# Dozimetr.net
KiCad netlist of a schematic drawn in EAGLE
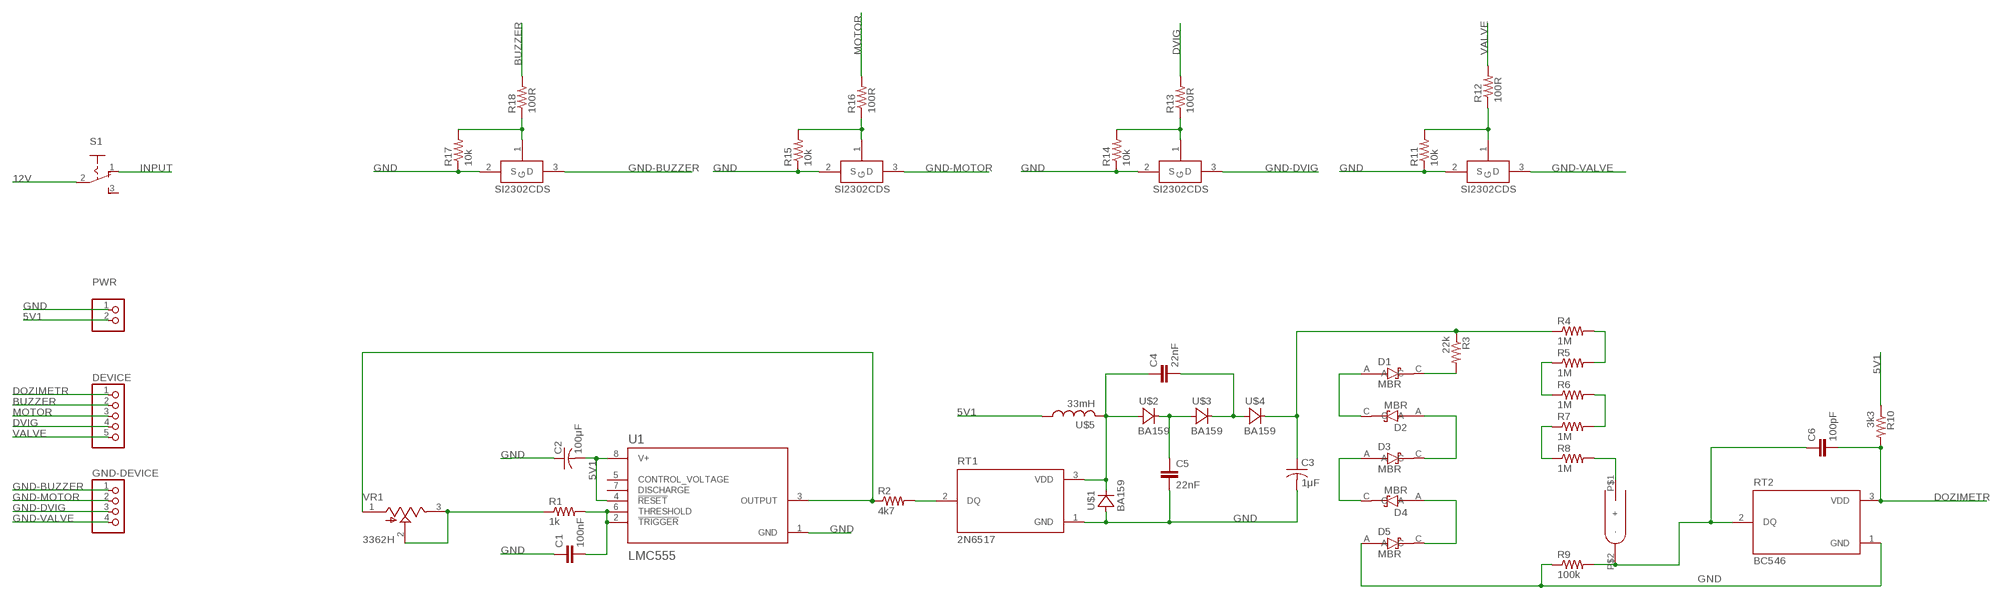
[diagram p0: schematic, sheet 1]

(export (version "E")
  (design (tool "Eeschema 10.0.6"))
  (components
    (comp (ref "C1")
      (value "100nF")
      (footprint "eagle-import:C0603")
      (libsource (lib "eagle-import") (part "C-EUC0603"))
    )
    (comp (ref "C2")
      (value "100μF")
      (footprint "eagle-import:ECAP100-CMD")
      (libsource (lib "eagle-import") (part "ECAPECAP100"))
    )
    (comp (ref "C3")
      (value "1μF")
      (footprint "eagle-import:ECAP1MK")
      (libsource (lib "eagle-import") (part "ECAP"))
    )
    (comp (ref "C4")
      (value "22nF")
      (footprint "eagle-import:C1210")
      (libsource (lib "eagle-import") (part "C-EUC1210"))
    )
    (comp (ref "C5")
      (value "22nF")
      (footprint "eagle-import:C1210")
      (libsource (lib "eagle-import") (part "C-EUC1210"))
    )
    (comp (ref "C6")
      (value "100pF")
      (footprint "eagle-import:C0603")
      (libsource (lib "eagle-import") (part "C-EUC0603"))
    )
    (comp (ref "D1")
      (value "MBR")
      (footprint "eagle-import:SOD123")
      (fields (field (name "MF") "ON Semiconductor") (field (name "MP") "MBR0520LT1G"))
      (libsource (lib "eagle-import") (part "DIODE-MBR"))
    )
    (comp (ref "D2")
      (value "MBR")
      (footprint "eagle-import:SOD123")
      (fields (field (name "MF") "ON Semiconductor") (field (name "MP") "MBR0520LT1G"))
      (libsource (lib "eagle-import") (part "DIODE-MBR"))
    )
    (comp (ref "D3")
      (value "MBR")
      (footprint "eagle-import:SOD123")
      (fields (field (name "MF") "ON Semiconductor") (field (name "MP") "MBR0520LT1G"))
      (libsource (lib "eagle-import") (part "DIODE-MBR"))
    )
    (comp (ref "D4")
      (value "MBR")
      (footprint "eagle-import:SOD123")
      (fields (field (name "MF") "ON Semiconductor") (field (name "MP") "MBR0520LT1G"))
      (libsource (lib "eagle-import") (part "DIODE-MBR"))
    )
    (comp (ref "D5")
      (value "MBR")
      (footprint "eagle-import:SOD123")
      (fields (field (name "MF") "ON Semiconductor") (field (name "MP") "MBR0520LT1G"))
      (libsource (lib "eagle-import") (part "DIODE-MBR"))
    )
    (comp (ref "DEVICE")
      (value "PINHD-1X5")
      (footprint "eagle-import:1X05")
      (libsource (lib "eagle-import") (part "PINHD-1X5"))
    )
    (comp (ref "DOSE")
      (value "DOSIM_SBM20-1")
      (footprint "eagle-import:DOSIM_SBM20-1")
      (libsource (lib "eagle-import") (part "DOSIM_SBM20-1"))
    )
    (comp (ref "GND-DEVICE")
      (value "PINHD-1X4")
      (footprint "eagle-import:1X04")
      (libsource (lib "eagle-import") (part "PINHD-1X4"))
    )
    (comp (ref "PWR")
      (value "PINHD-1X2")
      (footprint "eagle-import:1X02")
      (libsource (lib "eagle-import") (part "PINHD-1X2"))
    )
    (comp (ref "R1")
      (value "1k")
      (footprint "eagle-import:R0603")
      (libsource (lib "eagle-import") (part "R-US_R0603"))
    )
    (comp (ref "R2")
      (value "4k7")
      (footprint "eagle-import:R0603")
      (libsource (lib "eagle-import") (part "R-US_R0603"))
    )
    (comp (ref "R3")
      (value "22k")
      (footprint "eagle-import:R0603")
      (libsource (lib "eagle-import") (part "R-US_R0603"))
    )
    (comp (ref "R4")
      (value "1M")
      (footprint "eagle-import:R0603")
      (libsource (lib "eagle-import") (part "R-US_R0603"))
    )
    (comp (ref "R5")
      (value "1M")
      (footprint "eagle-import:R0603")
      (libsource (lib "eagle-import") (part "R-US_R0603"))
    )
    (comp (ref "R6")
      (value "1M")
      (footprint "eagle-import:R0603")
      (libsource (lib "eagle-import") (part "R-US_R0603"))
    )
    (comp (ref "R7")
      (value "1M")
      (footprint "eagle-import:R0603")
      (libsource (lib "eagle-import") (part "R-US_R0603"))
    )
    (comp (ref "R8")
      (value "1M")
      (footprint "eagle-import:R0603")
      (libsource (lib "eagle-import") (part "R-US_R0603"))
    )
    (comp (ref "R9")
      (value "100k")
      (footprint "eagle-import:R0603")
      (libsource (lib "eagle-import") (part "R-US_R0603"))
    )
    (comp (ref "R10")
      (value "3k3")
      (footprint "eagle-import:R0603")
      (libsource (lib "eagle-import") (part "R-US_R0603"))
    )
    (comp (ref "R11")
      (value "10k")
      (footprint "eagle-import:R0603")
      (libsource (lib "eagle-import") (part "R-US_R0603"))
    )
    (comp (ref "R12")
      (value "100R")
      (footprint "eagle-import:R0603")
      (libsource (lib "eagle-import") (part "R-US_R0603"))
    )
    (comp (ref "R13")
      (value "100R")
      (footprint "eagle-import:R0603")
      (libsource (lib "eagle-import") (part "R-US_R0603"))
    )
    (comp (ref "R14")
      (value "10k")
      (footprint "eagle-import:R0603")
      (libsource (lib "eagle-import") (part "R-US_R0603"))
    )
    (comp (ref "R15")
      (value "10k")
      (footprint "eagle-import:R0603")
      (libsource (lib "eagle-import") (part "R-US_R0603"))
    )
    (comp (ref "R16")
      (value "100R")
      (footprint "eagle-import:R0603")
      (libsource (lib "eagle-import") (part "R-US_R0603"))
    )
    (comp (ref "R17")
      (value "10k")
      (footprint "eagle-import:R0603")
      (libsource (lib "eagle-import") (part "R-US_R0603"))
    )
    (comp (ref "R18")
      (value "100R")
      (footprint "eagle-import:R0603")
      (libsource (lib "eagle-import") (part "R-US_R0603"))
    )
    (comp (ref "RT1")
      (value "2N6517")
      (footprint "eagle-import:TO92_TO226")
      (fields (field (name "MF") "Maxim Integrated") (field (name "MP") "DS1820"))
      (libsource (lib "eagle-import") (part "2N6517"))
    )
    (comp (ref "RT2")
      (value "BC546")
      (footprint "eagle-import:TO92_TO226")
      (fields (field (name "MF") "Maxim Integrated") (field (name "MP") "DS1820"))
      (libsource (lib "eagle-import") (part "BC546"))
    )
    (comp (ref "S1")
      (value "SWITCH-BIG")
      (footprint "eagle-import:SWITCH-BIG")
      (libsource (lib "eagle-import") (part "SWITCH-BIG"))
    )
    (comp (ref "SI2302-1")
      (value "SI2302CDS")
      (footprint "eagle-import:SOT23-3")
      (libsource (lib "eagle-import") (part "SI2302CDS"))
    )
    (comp (ref "SI2302-2")
      (value "SI2302CDS")
      (footprint "eagle-import:SOT23-3")
      (libsource (lib "eagle-import") (part "SI2302CDS"))
    )
    (comp (ref "SI2302-3")
      (value "SI2302CDS")
      (footprint "eagle-import:SOT23-3")
      (libsource (lib "eagle-import") (part "SI2302CDS"))
    )
    (comp (ref "SI2302-4")
      (value "SI2302CDS")
      (footprint "eagle-import:SOT23-3")
      (libsource (lib "eagle-import") (part "SI2302CDS"))
    )
    (comp (ref "U$1")
      (value "BA159")
      (footprint "eagle-import:BA159")
      (libsource (lib "eagle-import") (part "BA159"))
    )
    (comp (ref "U$2")
      (value "BA159")
      (footprint "eagle-import:BA159")
      (libsource (lib "eagle-import") (part "BA159"))
    )
    (comp (ref "U$3")
      (value "BA159")
      (footprint "eagle-import:BA159")
      (libsource (lib "eagle-import") (part "BA159"))
    )
    (comp (ref "U$4")
      (value "BA159")
      (footprint "eagle-import:BA159")
      (libsource (lib "eagle-import") (part "BA159"))
    )
    (comp (ref "U$5")
      (value "33mH")
      (footprint "eagle-import:RCH114NP_-")
      (libsource (lib "eagle-import") (part "RCH114NP"))
    )
    (comp (ref "U1")
      (value "LMC555")
      (footprint "eagle-import:SOIC127P599X175-8N")
      (fields (field (name "MF") "Texas Instruments") (field (name "MP") "LMC555CMX"))
      (libsource (lib "eagle-import") (part "LMC555CMX/NOPB"))
    )
    (comp (ref "VR1")
      (value "3362H")
      (footprint "eagle-import:TRIM_3362H-1-502LF")
      (fields (field (name "MF") "Bourns") (field (name "MP") "3362P-1-502LF"))
      (libsource (lib "eagle-import") (part "3362H-1-502LF"))
    )
  )
  (nets
    (net (code "1") (name "/5V1") (class "Default")
      (node (ref "C2") (pin "P$2") (pinfunction "2_P$2") (pintype "passive"))
      (node (ref "PWR") (pin "2") (pinfunction "2_2") (pintype "passive"))
      (node (ref "R10") (pin "1") (pinfunction "1_1") (pintype "passive"))
      (node (ref "U$5") (pin "P$1") (pinfunction "1_P$1") (pintype "passive"))
      (node (ref "U1") (pin "4") (pinfunction "~{RESET}_4") (pintype "input"))
      (node (ref "U1") (pin "8") (pinfunction "V+_8") (pintype "power_in"))
    )
    (net (code "2") (name "/12V") (class "Default")
      (node (ref "S1") (pin "2") (pinfunction "P_2") (pintype "passive"))
    )
    (net (code "3") (name "/BUZZER") (class "Default")
      (node (ref "DEVICE") (pin "2") (pinfunction "2_2") (pintype "passive"))
      (node (ref "R18") (pin "2") (pinfunction "2_2") (pintype "passive"))
    )
    (net (code "4") (name "/DOZIMETR") (class "Default")
      (node (ref "C6") (pin "2") (pinfunction "2_2") (pintype "passive"))
      (node (ref "DEVICE") (pin "1") (pinfunction "1_1") (pintype "passive"))
      (node (ref "R10") (pin "2") (pinfunction "2_2") (pintype "passive"))
      (node (ref "RT2") (pin "3") (pinfunction "VDD_3") (pintype "power_in"))
    )
    (net (code "5") (name "/DVIG") (class "Default")
      (node (ref "DEVICE") (pin "4") (pinfunction "4_4") (pintype "passive"))
      (node (ref "R13") (pin "2") (pinfunction "2_2") (pintype "passive"))
    )
    (net (code "6") (name "/GND") (class "Default")
      (node (ref "C1") (pin "1") (pinfunction "1_1") (pintype "passive"))
      (node (ref "C2") (pin "P$1") (pinfunction "1_P$1") (pintype "passive"))
      (node (ref "C3") (pin "P$2") (pinfunction "2_P$2") (pintype "passive"))
      (node (ref "C5") (pin "2") (pinfunction "2_2") (pintype "passive"))
      (node (ref "D5") (pin "A") (pinfunction "A_A") (pintype "passive"))
      (node (ref "PWR") (pin "1") (pinfunction "1_1") (pintype "passive"))
      (node (ref "R11") (pin "1") (pinfunction "1_1") (pintype "passive"))
      (node (ref "R14") (pin "1") (pinfunction "1_1") (pintype "passive"))
      (node (ref "R15") (pin "1") (pinfunction "1_1") (pintype "passive"))
      (node (ref "R17") (pin "1") (pinfunction "1_1") (pintype "passive"))
      (node (ref "R9") (pin "1") (pinfunction "1_1") (pintype "passive"))
      (node (ref "RT1") (pin "1") (pinfunction "GND_1") (pintype "power_in"))
      (node (ref "RT2") (pin "1") (pinfunction "GND_1") (pintype "power_in"))
      (node (ref "SI2302-1") (pin "2") (pinfunction "S_2") (pintype "bidirectional"))
      (node (ref "SI2302-2") (pin "2") (pinfunction "S_2") (pintype "bidirectional"))
      (node (ref "SI2302-3") (pin "2") (pinfunction "S_2") (pintype "bidirectional"))
      (node (ref "SI2302-4") (pin "2") (pinfunction "S_2") (pintype "bidirectional"))
      (node (ref "U$1") (pin "P$1") (pinfunction "A_P$1") (pintype "passive"))
      (node (ref "U1") (pin "1") (pinfunction "GND_1") (pintype "power_in"))
    )
    (net (code "7") (name "/GND-BUZZER") (class "Default")
      (node (ref "GND-DEVICE") (pin "1") (pinfunction "1_1") (pintype "passive"))
      (node (ref "SI2302-1") (pin "3") (pinfunction "D_3") (pintype "bidirectional"))
    )
    (net (code "8") (name "/GND-DVIG") (class "Default")
      (node (ref "GND-DEVICE") (pin "3") (pinfunction "3_3") (pintype "passive"))
      (node (ref "SI2302-3") (pin "3") (pinfunction "D_3") (pintype "bidirectional"))
    )
    (net (code "9") (name "/GND-MOTOR") (class "Default")
      (node (ref "GND-DEVICE") (pin "2") (pinfunction "2_2") (pintype "passive"))
      (node (ref "SI2302-2") (pin "3") (pinfunction "D_3") (pintype "bidirectional"))
    )
    (net (code "10") (name "/GND-VALVE") (class "Default")
      (node (ref "GND-DEVICE") (pin "4") (pinfunction "4_4") (pintype "passive"))
      (node (ref "SI2302-4") (pin "3") (pinfunction "D_3") (pintype "bidirectional"))
    )
    (net (code "11") (name "/INPUT") (class "Default")
      (node (ref "S1") (pin "1") (pinfunction "O_1") (pintype "passive"))
    )
    (net (code "12") (name "/MOTOR") (class "Default")
      (node (ref "DEVICE") (pin "3") (pinfunction "3_3") (pintype "passive"))
      (node (ref "R16") (pin "2") (pinfunction "2_2") (pintype "passive"))
    )
    (net (code "13") (name "/VALVE") (class "Default")
      (node (ref "DEVICE") (pin "5") (pinfunction "5_5") (pintype "passive"))
      (node (ref "R12") (pin "2") (pinfunction "2_2") (pintype "passive"))
    )
    (net (code "14") (name "Net-(C3-1)") (class "Default")
      (node (ref "C3") (pin "P$1") (pinfunction "1_P$1") (pintype "passive"))
      (node (ref "R3") (pin "1") (pinfunction "1_1") (pintype "passive"))
      (node (ref "R4") (pin "1") (pinfunction "1_1") (pintype "passive"))
      (node (ref "U$4") (pin "P$2") (pinfunction "C_P$2") (pintype "passive"))
    )
    (net (code "15") (name "Net-(D1-PadA)") (class "Default")
      (node (ref "D1") (pin "A") (pinfunction "A_A") (pintype "passive"))
      (node (ref "D2") (pin "C") (pinfunction "C_C") (pintype "passive"))
    )
    (net (code "16") (name "Net-(D1-PadC)") (class "Default")
      (node (ref "D1") (pin "C") (pinfunction "C_C") (pintype "passive"))
      (node (ref "R3") (pin "2") (pinfunction "2_2") (pintype "passive"))
    )
    (net (code "17") (name "Net-(D2-PadA)") (class "Default")
      (node (ref "D2") (pin "A") (pinfunction "A_A") (pintype "passive"))
      (node (ref "D3") (pin "C") (pinfunction "C_C") (pintype "passive"))
    )
    (net (code "18") (name "Net-(D3-PadA)") (class "Default")
      (node (ref "D3") (pin "A") (pinfunction "A_A") (pintype "passive"))
      (node (ref "D4") (pin "C") (pinfunction "C_C") (pintype "passive"))
    )
    (net (code "19") (name "Net-(D4-PadA)") (class "Default")
      (node (ref "D4") (pin "A") (pinfunction "A_A") (pintype "passive"))
      (node (ref "D5") (pin "C") (pinfunction "C_C") (pintype "passive"))
    )
    (net (code "20") (name "Net-(DOSE-+)") (class "Default")
      (node (ref "DOSE") (pin "P$1") (pinfunction "+_P$1") (pintype "bidirectional"))
      (node (ref "R8") (pin "2") (pinfunction "2_2") (pintype "passive"))
    )
    (net (code "21") (name "Net-(DOSE--)") (class "Default")
      (node (ref "C6") (pin "1") (pinfunction "1_1") (pintype "passive"))
      (node (ref "DOSE") (pin "P$2") (pinfunction "-_P$2") (pintype "bidirectional"))
      (node (ref "R9") (pin "2") (pinfunction "2_2") (pintype "passive"))
      (node (ref "RT2") (pin "2") (pinfunction "DQ_2") (pintype "bidirectional"))
    )
    (net (code "22") (name "Net-(R4-Pad2)") (class "Default")
      (node (ref "R4") (pin "2") (pinfunction "2_2") (pintype "passive"))
      (node (ref "R5") (pin "2") (pinfunction "2_2") (pintype "passive"))
    )
    (net (code "23") (name "Net-(R5-Pad1)") (class "Default")
      (node (ref "R5") (pin "1") (pinfunction "1_1") (pintype "passive"))
      (node (ref "R6") (pin "1") (pinfunction "1_1") (pintype "passive"))
    )
    (net (code "24") (name "Net-(R6-Pad2)") (class "Default")
      (node (ref "R6") (pin "2") (pinfunction "2_2") (pintype "passive"))
      (node (ref "R7") (pin "2") (pinfunction "2_2") (pintype "passive"))
    )
    (net (code "25") (name "Net-(R7-Pad1)") (class "Default")
      (node (ref "R7") (pin "1") (pinfunction "1_1") (pintype "passive"))
      (node (ref "R8") (pin "1") (pinfunction "1_1") (pintype "passive"))
    )
    (net (code "26") (name "Net-(RT1-DQ)") (class "Default")
      (node (ref "R2") (pin "2") (pinfunction "2_2") (pintype "passive"))
      (node (ref "RT1") (pin "2") (pinfunction "DQ_2") (pintype "bidirectional"))
    )
    (net (code "27") (name "Net-(RT1-VDD)") (class "Default")
      (node (ref "C4") (pin "1") (pinfunction "1_1") (pintype "passive"))
      (node (ref "RT1") (pin "3") (pinfunction "VDD_3") (pintype "power_in"))
      (node (ref "U$1") (pin "P$2") (pinfunction "C_P$2") (pintype "passive"))
      (node (ref "U$2") (pin "P$1") (pinfunction "A_P$1") (pintype "passive"))
      (node (ref "U$5") (pin "P$2") (pinfunction "2_P$2") (pintype "passive"))
    )
    (net (code "28") (name "Net-(SI2302-1-G)") (class "Default")
      (node (ref "R17") (pin "2") (pinfunction "2_2") (pintype "passive"))
      (node (ref "R18") (pin "1") (pinfunction "1_1") (pintype "passive"))
      (node (ref "SI2302-1") (pin "1") (pinfunction "G_1") (pintype "bidirectional"))
    )
    (net (code "29") (name "Net-(SI2302-2-G)") (class "Default")
      (node (ref "R15") (pin "2") (pinfunction "2_2") (pintype "passive"))
      (node (ref "R16") (pin "1") (pinfunction "1_1") (pintype "passive"))
      (node (ref "SI2302-2") (pin "1") (pinfunction "G_1") (pintype "bidirectional"))
    )
    (net (code "30") (name "Net-(SI2302-3-G)") (class "Default")
      (node (ref "R13") (pin "1") (pinfunction "1_1") (pintype "passive"))
      (node (ref "R14") (pin "2") (pinfunction "2_2") (pintype "passive"))
      (node (ref "SI2302-3") (pin "1") (pinfunction "G_1") (pintype "bidirectional"))
    )
    (net (code "31") (name "Net-(SI2302-4-G)") (class "Default")
      (node (ref "R11") (pin "2") (pinfunction "2_2") (pintype "passive"))
      (node (ref "R12") (pin "1") (pinfunction "1_1") (pintype "passive"))
      (node (ref "SI2302-4") (pin "1") (pinfunction "G_1") (pintype "bidirectional"))
    )
    (net (code "32") (name "Net-(U$2-C)") (class "Default")
      (node (ref "C5") (pin "1") (pinfunction "1_1") (pintype "passive"))
      (node (ref "U$2") (pin "P$2") (pinfunction "C_P$2") (pintype "passive"))
      (node (ref "U$3") (pin "P$1") (pinfunction "A_P$1") (pintype "passive"))
    )
    (net (code "33") (name "Net-(U$3-C)") (class "Default")
      (node (ref "C4") (pin "2") (pinfunction "2_2") (pintype "passive"))
      (node (ref "U$3") (pin "P$2") (pinfunction "C_P$2") (pintype "passive"))
      (node (ref "U$4") (pin "P$1") (pinfunction "A_P$1") (pintype "passive"))
    )
    (net (code "34") (name "Net-(U1-OUTPUT)") (class "Default")
      (node (ref "R2") (pin "1") (pinfunction "1_1") (pintype "passive"))
      (node (ref "U1") (pin "3") (pinfunction "OUTPUT_3") (pintype "output"))
      (node (ref "VR1") (pin "1") (pinfunction "CCW_1") (pintype "passive"))
    )
    (net (code "35") (name "Net-(U1-THRESHOLD)") (class "Default")
      (node (ref "C1") (pin "2") (pinfunction "2_2") (pintype "passive"))
      (node (ref "R1") (pin "2") (pinfunction "2_2") (pintype "passive"))
      (node (ref "U1") (pin "2") (pinfunction "~{TRIGGER}_2") (pintype "input"))
      (node (ref "U1") (pin "6") (pinfunction "THRESHOLD_6") (pintype "input"))
    )
    (net (code "36") (name "Net-(VR1-CW)") (class "Default")
      (node (ref "R1") (pin "1") (pinfunction "1_1") (pintype "passive"))
      (node (ref "VR1") (pin "2") (pinfunction "WIPER_2") (pintype "passive"))
      (node (ref "VR1") (pin "3") (pinfunction "CW_3") (pintype "passive"))
    )
    (net (code "37") (name "unconnected-(S1-S-Pad3)") (class "Default")
      (node (ref "S1") (pin "3") (pinfunction "S_3") (pintype "passive"))
    )
    (net (code "38") (name "unconnected-(U1-CONTROL_VOLTAGE-Pad5)") (class "Default")
      (node (ref "U1") (pin "5") (pinfunction "CONTROL_VOLTAGE_5") (pintype "input"))
    )
    (net (code "39") (name "unconnected-(U1-DISCHARGE-Pad7)") (class "Default")
      (node (ref "U1") (pin "7") (pinfunction "DISCHARGE_7") (pintype "input"))
    )
  )
)
